# Sheet.net
KiCad netlist of a schematic drawn in Altium Designer
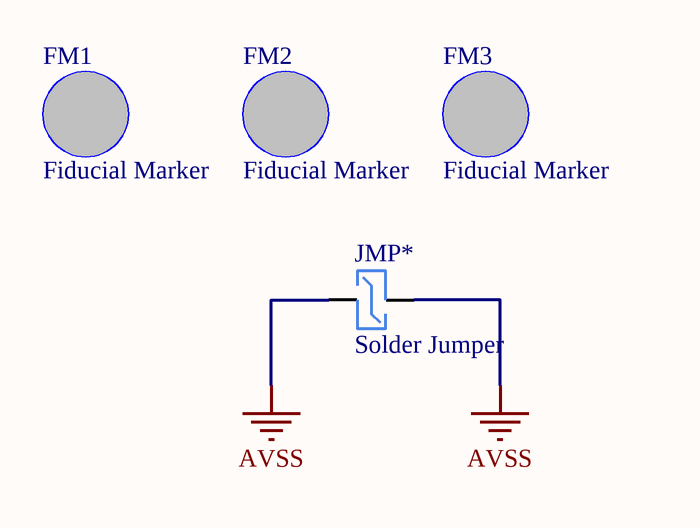
[diagram p0: Sheet.SchDoc]

(export (version "E")
  (design (tool "Eeschema 10.0.6"))
  (components
    (comp (ref "FM1")
      (value "Fiducial Marker")
      (footprint "Fiducial Marker-Footprint-1")
      (description "fancy style")
      (libsource (lib "ART-TU Cluj-Napoca") (part "FM?"))
    )
    (comp (ref "FM2")
      (value "Fiducial Marker")
      (footprint "Fiducial Marker-Footprint-1")
      (description "fancy style")
      (libsource (lib "ART-TU Cluj-Napoca") (part "FM?"))
    )
    (comp (ref "FM3")
      (value "Fiducial Marker")
      (footprint "Fiducial Marker-Footprint-1")
      (description "fancy style")
      (libsource (lib "ART-TU Cluj-Napoca") (part "FM?"))
    )
    (comp (ref "JMP*")
      (value "Solder Jumper")
      (footprint "Solder Jumper-Footprint-1")
      (description "2 port solder jumper")
      (libsource (lib "goulash den") (part "Jumper"))
    )
  )
  (nets
    (net (code "1") (name "AVSS") (class "Default")
      (node (ref "JMP*") (pin "1") (pinfunction "1_1") (pintype "passive"))
      (node (ref "JMP*") (pin "2") (pinfunction "2_2") (pintype "passive"))
    )
  )
)
